# HUB.net
KiCad netlist of a schematic drawn in Altium Designer
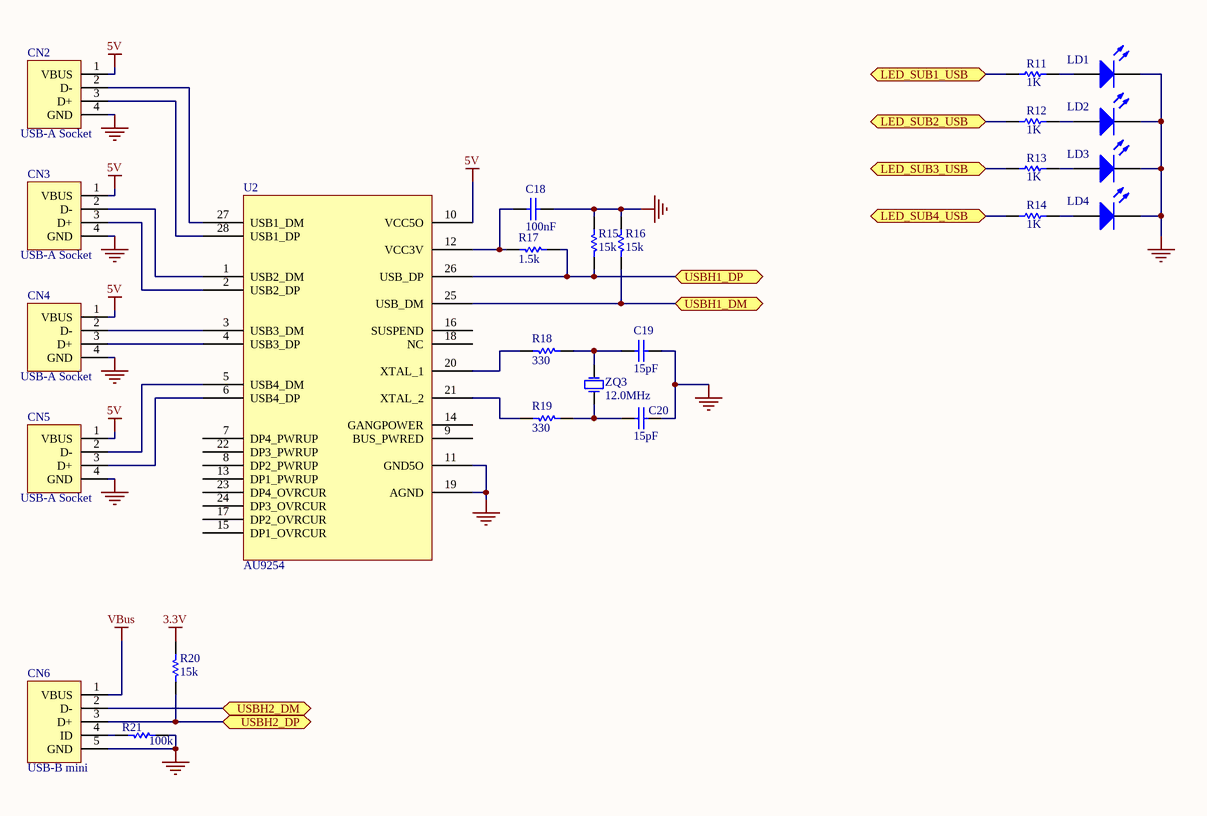
[diagram p0: HUB.SchDoc]

(export (version "E")
  (design (tool "Eeschema 10.0.6"))
  (components
    (comp (ref "C18")
      (value "100nF")
      (footprint "RAD-0.3")
      (description "Capacitor")
      (fields (field (name "Comment") "Cap") (field (name "PUBLISHER") "Altium Limited"))
      (libsource (lib "Miscellaneous Devices") (part "Cap"))
    )
    (comp (ref "C19")
      (value "15pF")
      (footprint "RAD-0.3")
      (description "Capacitor")
      (fields (field (name "Comment") "Cap") (field (name "PUBLISHER") "Altium Limited"))
      (libsource (lib "Miscellaneous Devices") (part "Cap"))
    )
    (comp (ref "C20")
      (value "15pF")
      (footprint "RAD-0.3")
      (description "Capacitor")
      (fields (field (name "Comment") "Cap") (field (name "PUBLISHER") "Altium Limited"))
      (libsource (lib "Miscellaneous Devices") (part "Cap"))
    )
    (comp (ref "CN2")
      (value "USB-A Socket")
      (footprint "1470695")
      (description "USB 1.1, Right Angle, SMT, A Type, Plug, 4 Position, Black")
      (fields (field (name "PUBLISHER") "Altium Limited"))
      (libsource (lib "AU9254") (part "USB-A"))
    )
    (comp (ref "CN3")
      (value "USB-A Socket")
      (footprint "1470695")
      (description "USB 1.1, Right Angle, SMT, A Type, Plug, 4 Position, Black")
      (fields (field (name "PUBLISHER") "Altium Limited"))
      (libsource (lib "AU9254") (part "USB-A"))
    )
    (comp (ref "CN4")
      (value "USB-A Socket")
      (footprint "1470695")
      (description "USB 1.1, Right Angle, SMT, A Type, Plug, 4 Position, Black")
      (fields (field (name "PUBLISHER") "Altium Limited"))
      (libsource (lib "AU9254") (part "USB-A"))
    )
    (comp (ref "CN5")
      (value "USB-A Socket")
      (footprint "1470695")
      (description "USB 1.1, Right Angle, SMT, A Type, Plug, 4 Position, Black")
      (fields (field (name "PUBLISHER") "Altium Limited"))
      (libsource (lib "AU9254") (part "USB-A"))
    )
    (comp (ref "CN6")
      (value "USB-B mini")
      (footprint "USB_micro-B")
      (libsource (lib "AU9254") (part "USB-B mini"))
    )
    (comp (ref "LD1")
      (value "LED1")
      (footprint "LED-1")
      (description "Typical RED GaAs LED")
      (fields (field (name "PUBLISHER") "Altium Limited"))
      (libsource (lib "Miscellaneous Devices") (part "LED1"))
    )
    (comp (ref "LD2")
      (value "LED1")
      (footprint "LED-1")
      (description "Typical RED GaAs LED")
      (fields (field (name "PUBLISHER") "Altium Limited"))
      (libsource (lib "Miscellaneous Devices") (part "LED1"))
    )
    (comp (ref "LD3")
      (value "LED1")
      (footprint "LED-1")
      (description "Typical RED GaAs LED")
      (fields (field (name "PUBLISHER") "Altium Limited"))
      (libsource (lib "Miscellaneous Devices") (part "LED1"))
    )
    (comp (ref "LD4")
      (value "LED1")
      (footprint "LED-1")
      (description "Typical RED GaAs LED")
      (fields (field (name "PUBLISHER") "Altium Limited"))
      (libsource (lib "Miscellaneous Devices") (part "LED1"))
    )
    (comp (ref "R11")
      (value "1K")
      (footprint "AXIAL-0.3")
      (description "Resistor")
      (fields (field (name "Comment") "Res1") (field (name "PUBLISHER") "Altium Limited"))
      (libsource (lib "Miscellaneous Devices") (part "Res1"))
    )
    (comp (ref "R12")
      (value "1K")
      (footprint "AXIAL-0.3")
      (description "Resistor")
      (fields (field (name "Comment") "Res1") (field (name "PUBLISHER") "Altium Limited"))
      (libsource (lib "Miscellaneous Devices") (part "Res1"))
    )
    (comp (ref "R13")
      (value "1K")
      (footprint "AXIAL-0.3")
      (description "Resistor")
      (fields (field (name "Comment") "Res1") (field (name "PUBLISHER") "Altium Limited"))
      (libsource (lib "Miscellaneous Devices") (part "Res1"))
    )
    (comp (ref "R14")
      (value "1K")
      (footprint "AXIAL-0.3")
      (description "Resistor")
      (fields (field (name "Comment") "Res1") (field (name "PUBLISHER") "Altium Limited"))
      (libsource (lib "Miscellaneous Devices") (part "Res1"))
    )
    (comp (ref "R15")
      (value "15k")
      (footprint "AXIAL-0.3")
      (description "Resistor")
      (fields (field (name "Comment") "Res1") (field (name "PUBLISHER") "Altium Limited"))
      (libsource (lib "Miscellaneous Devices") (part "Res1"))
    )
    (comp (ref "R16")
      (value "15k")
      (footprint "AXIAL-0.3")
      (description "Resistor")
      (fields (field (name "Comment") "Res1") (field (name "PUBLISHER") "Altium Limited"))
      (libsource (lib "Miscellaneous Devices") (part "Res1"))
    )
    (comp (ref "R17")
      (value "1.5k")
      (footprint "AXIAL-0.3")
      (description "Resistor")
      (fields (field (name "Comment") "Res1") (field (name "PUBLISHER") "Altium Limited"))
      (libsource (lib "Miscellaneous Devices") (part "Res1"))
    )
    (comp (ref "R18")
      (value "330")
      (footprint "AXIAL-0.3")
      (description "Resistor")
      (fields (field (name "Comment") "Res1") (field (name "PUBLISHER") "Altium Limited"))
      (libsource (lib "Miscellaneous Devices") (part "Res1"))
    )
    (comp (ref "R19")
      (value "330")
      (footprint "AXIAL-0.3")
      (description "Resistor")
      (fields (field (name "Comment") "Res1") (field (name "PUBLISHER") "Altium Limited"))
      (libsource (lib "Miscellaneous Devices") (part "Res1"))
    )
    (comp (ref "R20")
      (value "15k")
      (footprint "AXIAL-0.3")
      (description "Resistor")
      (fields (field (name "Comment") "Res1") (field (name "PUBLISHER") "Altium Limited"))
      (libsource (lib "Miscellaneous Devices") (part "Res1"))
    )
    (comp (ref "R21")
      (value "100k")
      (footprint "AXIAL-0.3")
      (description "Resistor")
      (fields (field (name "Comment") "Res1") (field (name "PUBLISHER") "Altium Limited"))
      (libsource (lib "Miscellaneous Devices") (part "Res1"))
    )
    (comp (ref "U2") (value "AU9254") (libsource (lib "AU9254") (part "AU9254")))
    (comp (ref "ZQ3")
      (value "12.0MHz")
      (footprint "R38")
      (description "Crystal Oscillator")
      (fields (field (name "Comment") "XTAL") (field (name "PUBLISHER") "Altium Limited"))
      (libsource (lib "Miscellaneous Devices") (part "XTAL"))
    )
  )
  (nets
    (net (code "1") (name "/LED_SUB1_USB") (class "Default")
      (node (ref "R11") (pin "2") (pinfunction "2_2") (pintype "passive"))
    )
    (net (code "2") (name "/LED_SUB2_USB") (class "Default")
      (node (ref "R12") (pin "2") (pinfunction "2_2") (pintype "passive"))
    )
    (net (code "3") (name "/LED_SUB3_USB") (class "Default")
      (node (ref "R13") (pin "2") (pinfunction "2_2") (pintype "passive"))
    )
    (net (code "4") (name "/LED_SUB4_USB") (class "Default")
      (node (ref "R14") (pin "2") (pinfunction "2_2") (pintype "passive"))
    )
    (net (code "5") (name "/USBH1_DM") (class "Default")
      (node (ref "R16") (pin "1") (pinfunction "1_1") (pintype "passive"))
      (node (ref "U2") (pin "25") (pinfunction "USB_DM_25") (pintype "passive"))
    )
    (net (code "6") (name "/USBH1_DP") (class "Default")
      (node (ref "R15") (pin "1") (pinfunction "1_1") (pintype "passive"))
      (node (ref "R17") (pin "2") (pinfunction "2_2") (pintype "passive"))
      (node (ref "U2") (pin "26") (pinfunction "USB_DP_26") (pintype "passive"))
    )
    (net (code "7") (name "/USBH2_DM") (class "Default")
      (node (ref "CN6") (pin "2") (pinfunction "D-_2") (pintype "passive"))
    )
    (net (code "8") (name "/USBH2_DP") (class "Default")
      (node (ref "CN6") (pin "3") (pinfunction "D+_3") (pintype "passive"))
      (node (ref "R20") (pin "1") (pinfunction "1_1") (pintype "passive"))
    )
    (net (code "9") (name "3.3V") (class "Default")
      (node (ref "R20") (pin "2") (pinfunction "2_2") (pintype "passive"))
    )
    (net (code "10") (name "5V") (class "Default")
      (node (ref "CN2") (pin "1") (pinfunction "VBUS_1") (pintype "power_in"))
      (node (ref "CN3") (pin "1") (pinfunction "VBUS_1") (pintype "power_in"))
      (node (ref "CN4") (pin "1") (pinfunction "VBUS_1") (pintype "power_in"))
      (node (ref "CN5") (pin "1") (pinfunction "VBUS_1") (pintype "power_in"))
      (node (ref "U2") (pin "10") (pinfunction "VCC5O_10") (pintype "passive"))
    )
    (net (code "11") (name "GND") (class "Default")
      (node (ref "C18") (pin "2") (pinfunction "2_2") (pintype "passive"))
      (node (ref "C19") (pin "2") (pinfunction "2_2") (pintype "passive"))
      (node (ref "C20") (pin "2") (pinfunction "2_2") (pintype "passive"))
      (node (ref "CN2") (pin "4") (pinfunction "GND_4") (pintype "power_in"))
      (node (ref "CN3") (pin "4") (pinfunction "GND_4") (pintype "power_in"))
      (node (ref "CN4") (pin "4") (pinfunction "GND_4") (pintype "power_in"))
      (node (ref "CN5") (pin "4") (pinfunction "GND_4") (pintype "power_in"))
      (node (ref "CN6") (pin "5") (pinfunction "GND_5") (pintype "passive"))
      (node (ref "LD1") (pin "2") (pinfunction "K_2") (pintype "passive"))
      (node (ref "LD2") (pin "2") (pinfunction "K_2") (pintype "passive"))
      (node (ref "LD3") (pin "2") (pinfunction "K_2") (pintype "passive"))
      (node (ref "LD4") (pin "2") (pinfunction "K_2") (pintype "passive"))
      (node (ref "R15") (pin "2") (pinfunction "2_2") (pintype "passive"))
      (node (ref "R16") (pin "2") (pinfunction "2_2") (pintype "passive"))
      (node (ref "R21") (pin "2") (pinfunction "2_2") (pintype "passive"))
      (node (ref "U2") (pin "11") (pinfunction "GND5O_11") (pintype "passive"))
      (node (ref "U2") (pin "19") (pinfunction "AGND_19") (pintype "passive"))
    )
    (net (code "12") (name "Net-(CN2-D+)") (class "Default")
      (node (ref "CN2") (pin "3") (pinfunction "D+_3") (pintype "passive"))
      (node (ref "U2") (pin "28") (pinfunction "USB1_DP_28") (pintype "passive"))
    )
    (net (code "13") (name "Net-(CN2-D-)") (class "Default")
      (node (ref "CN2") (pin "2") (pinfunction "D-_2") (pintype "passive"))
      (node (ref "U2") (pin "27") (pinfunction "USB1_DM_27") (pintype "passive"))
    )
    (net (code "14") (name "Net-(CN3-D+)") (class "Default")
      (node (ref "CN3") (pin "3") (pinfunction "D+_3") (pintype "passive"))
      (node (ref "U2") (pin "2") (pinfunction "USB2_DP_2") (pintype "passive"))
    )
    (net (code "15") (name "Net-(CN3-D-)") (class "Default")
      (node (ref "CN3") (pin "2") (pinfunction "D-_2") (pintype "passive"))
      (node (ref "U2") (pin "1") (pinfunction "USB2_DM_1") (pintype "passive"))
    )
    (net (code "16") (name "Net-(CN4-D+)") (class "Default")
      (node (ref "CN4") (pin "3") (pinfunction "D+_3") (pintype "passive"))
      (node (ref "U2") (pin "4") (pinfunction "USB3_DP_4") (pintype "passive"))
    )
    (net (code "17") (name "Net-(CN4-D-)") (class "Default")
      (node (ref "CN4") (pin "2") (pinfunction "D-_2") (pintype "passive"))
      (node (ref "U2") (pin "3") (pinfunction "USB3_DM_3") (pintype "passive"))
    )
    (net (code "18") (name "Net-(CN5-D+)") (class "Default")
      (node (ref "CN5") (pin "3") (pinfunction "D+_3") (pintype "passive"))
      (node (ref "U2") (pin "6") (pinfunction "USB4_DP_6") (pintype "passive"))
    )
    (net (code "19") (name "Net-(CN5-D-)") (class "Default")
      (node (ref "CN5") (pin "2") (pinfunction "D-_2") (pintype "passive"))
      (node (ref "U2") (pin "5") (pinfunction "USB4_DM_5") (pintype "passive"))
    )
    (net (code "20") (name "Net-(CN6-ID)") (class "Default")
      (node (ref "CN6") (pin "4") (pinfunction "ID_4") (pintype "passive"))
      (node (ref "R21") (pin "1") (pinfunction "1_1") (pintype "passive"))
    )
    (net (code "21") (name "Net-(LD1-A)") (class "Default")
      (node (ref "LD1") (pin "1") (pinfunction "A_1") (pintype "passive"))
      (node (ref "R11") (pin "1") (pinfunction "1_1") (pintype "passive"))
    )
    (net (code "22") (name "Net-(LD2-A)") (class "Default")
      (node (ref "LD2") (pin "1") (pinfunction "A_1") (pintype "passive"))
      (node (ref "R12") (pin "1") (pinfunction "1_1") (pintype "passive"))
    )
    (net (code "23") (name "Net-(LD3-A)") (class "Default")
      (node (ref "LD3") (pin "1") (pinfunction "A_1") (pintype "passive"))
      (node (ref "R13") (pin "1") (pinfunction "1_1") (pintype "passive"))
    )
    (net (code "24") (name "Net-(LD4-A)") (class "Default")
      (node (ref "LD4") (pin "1") (pinfunction "A_1") (pintype "passive"))
      (node (ref "R14") (pin "1") (pinfunction "1_1") (pintype "passive"))
    )
    (net (code "25") (name "Net-(U2-VCC3V)") (class "Default")
      (node (ref "C18") (pin "1") (pinfunction "1_1") (pintype "passive"))
      (node (ref "R17") (pin "1") (pinfunction "1_1") (pintype "passive"))
      (node (ref "U2") (pin "12") (pinfunction "VCC3V_12") (pintype "passive"))
    )
    (net (code "26") (name "Net-(U2-XTAL_1)") (class "Default")
      (node (ref "R18") (pin "1") (pinfunction "1_1") (pintype "passive"))
      (node (ref "U2") (pin "20") (pinfunction "XTAL_1_20") (pintype "passive"))
    )
    (net (code "27") (name "Net-(U2-XTAL_2)") (class "Default")
      (node (ref "R19") (pin "1") (pinfunction "1_1") (pintype "passive"))
      (node (ref "U2") (pin "21") (pinfunction "XTAL_2_21") (pintype "passive"))
    )
    (net (code "28") (name "Net-(ZQ3-OSC1)") (class "Default")
      (node (ref "C20") (pin "1") (pinfunction "1_1") (pintype "passive"))
      (node (ref "R19") (pin "2") (pinfunction "2_2") (pintype "passive"))
      (node (ref "ZQ3") (pin "1") (pinfunction "OSC1_1") (pintype "passive"))
    )
    (net (code "29") (name "Net-(ZQ3-OSC2)") (class "Default")
      (node (ref "C19") (pin "1") (pinfunction "1_1") (pintype "passive"))
      (node (ref "R18") (pin "2") (pinfunction "2_2") (pintype "passive"))
      (node (ref "ZQ3") (pin "2") (pinfunction "OSC2_2") (pintype "passive"))
    )
    (net (code "30") (name "VBus") (class "Default")
      (node (ref "CN6") (pin "1") (pinfunction "VBUS_1") (pintype "passive"))
    )
    (net (code "31") (name "unconnected-(U2-BUS_PWRED-Pad9)") (class "Default")
      (node (ref "U2") (pin "9") (pinfunction "BUS_PWRED_9") (pintype "passive"))
    )
    (net (code "32") (name "unconnected-(U2-DP1_OVRCUR-Pad15)") (class "Default")
      (node (ref "U2") (pin "15") (pinfunction "DP1_OVRCUR_15") (pintype "passive"))
    )
    (net (code "33") (name "unconnected-(U2-DP1_PWRUP-Pad13)") (class "Default")
      (node (ref "U2") (pin "13") (pinfunction "DP1_PWRUP_13") (pintype "passive"))
    )
    (net (code "34") (name "unconnected-(U2-DP2_OVRCUR-Pad17)") (class "Default")
      (node (ref "U2") (pin "17") (pinfunction "DP2_OVRCUR_17") (pintype "passive"))
    )
    (net (code "35") (name "unconnected-(U2-DP2_PWRUP-Pad8)") (class "Default")
      (node (ref "U2") (pin "8") (pinfunction "DP2_PWRUP_8") (pintype "passive"))
    )
    (net (code "36") (name "unconnected-(U2-DP3_OVRCUR-Pad24)") (class "Default")
      (node (ref "U2") (pin "24") (pinfunction "DP3_OVRCUR_24") (pintype "passive"))
    )
    (net (code "37") (name "unconnected-(U2-DP3_PWRUP-Pad22)") (class "Default")
      (node (ref "U2") (pin "22") (pinfunction "DP3_PWRUP_22") (pintype "passive"))
    )
    (net (code "38") (name "unconnected-(U2-DP4_OVRCUR-Pad23)") (class "Default")
      (node (ref "U2") (pin "23") (pinfunction "DP4_OVRCUR_23") (pintype "passive"))
    )
    (net (code "39") (name "unconnected-(U2-DP4_PWRUP-Pad7)") (class "Default")
      (node (ref "U2") (pin "7") (pinfunction "DP4_PWRUP_7") (pintype "passive"))
    )
    (net (code "40") (name "unconnected-(U2-GANGPOWER-Pad14)") (class "Default")
      (node (ref "U2") (pin "14") (pinfunction "GANGPOWER_14") (pintype "passive"))
    )
    (net (code "41") (name "unconnected-(U2-NC-Pad18)") (class "Default")
      (node (ref "U2") (pin "18") (pinfunction "NC_18") (pintype "passive"))
    )
    (net (code "42") (name "unconnected-(U2-SUSPEND-Pad16)") (class "Default")
      (node (ref "U2") (pin "16") (pinfunction "SUSPEND_16") (pintype "passive"))
    )
  )
)
